# raspberrypi-testcard.net
KiCad netlist of a schematic drawn in EAGLE
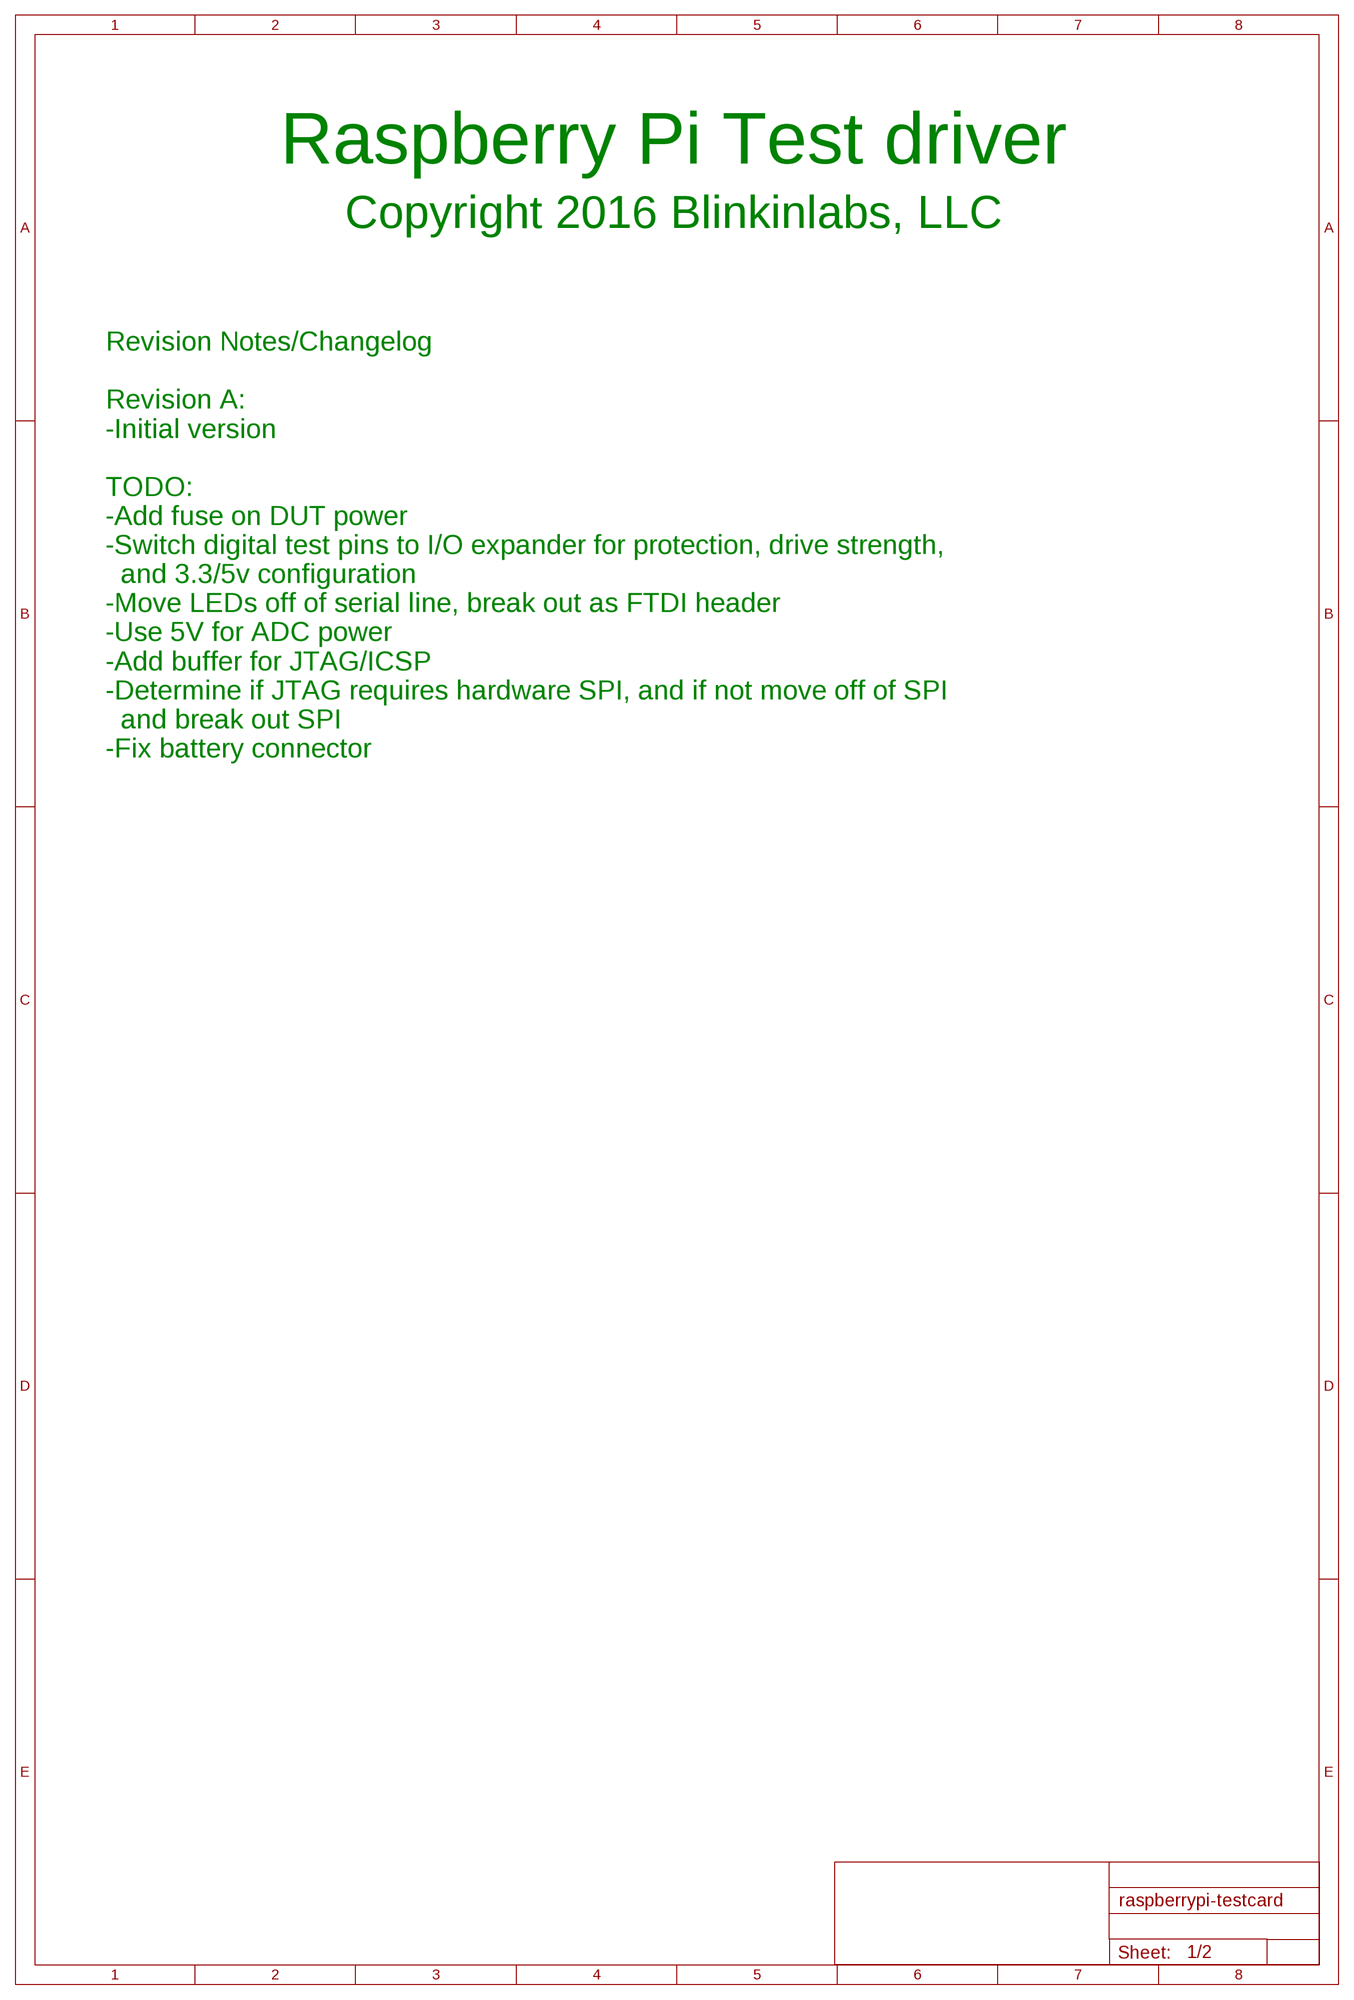
[diagram p0: schematic, sheet 1]
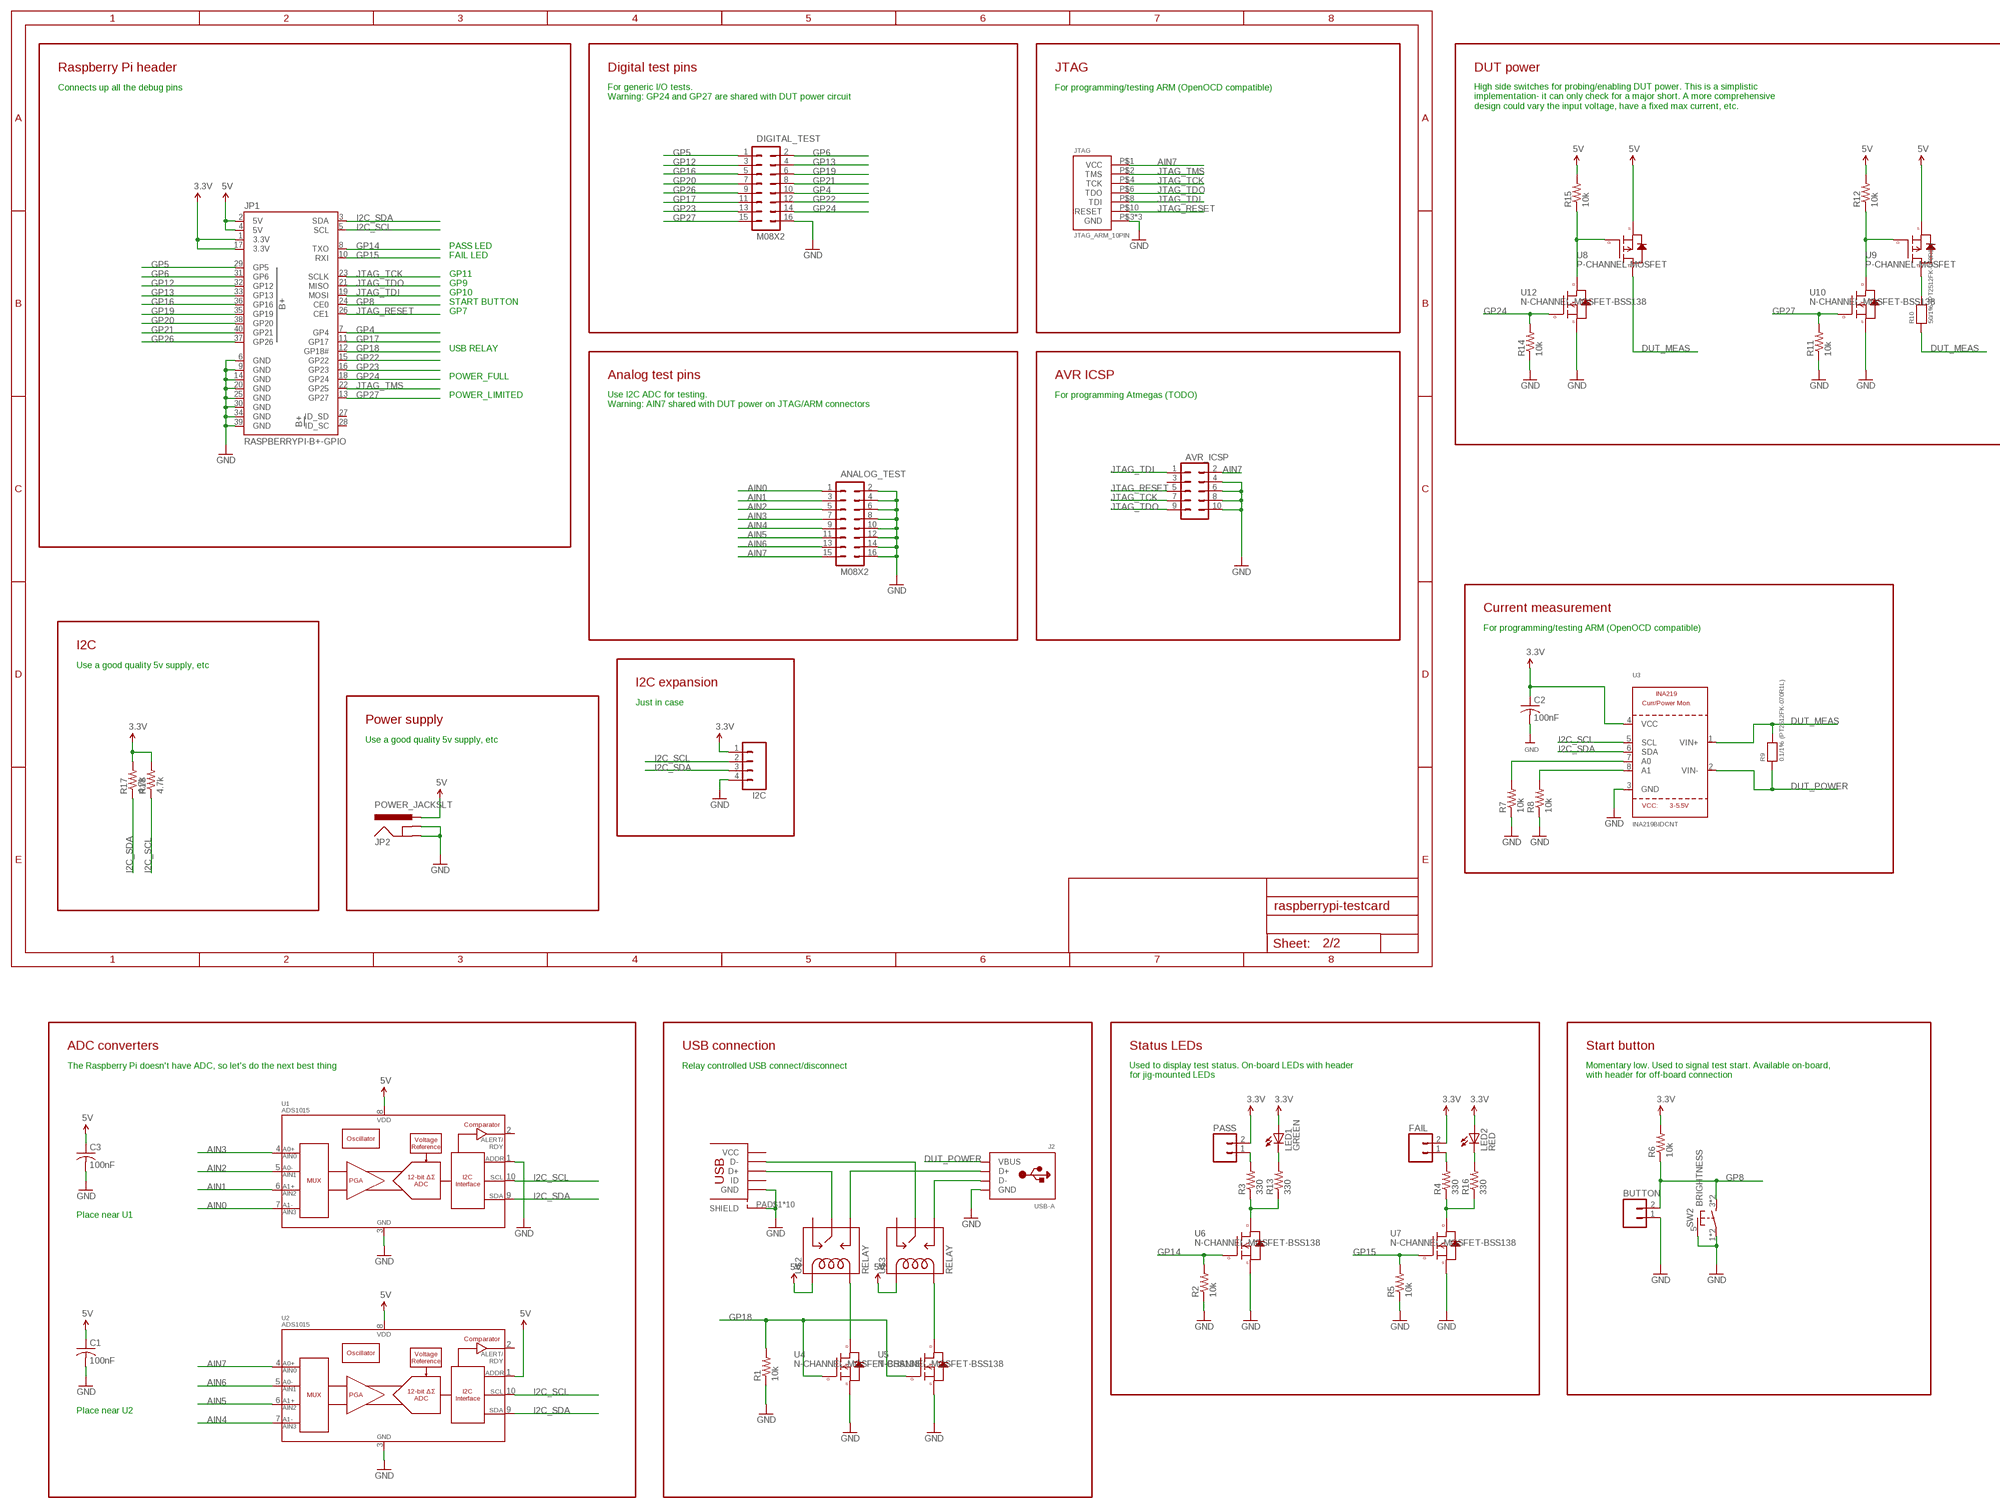
[diagram p1: schematic, sheet 2, part 1 of 2]
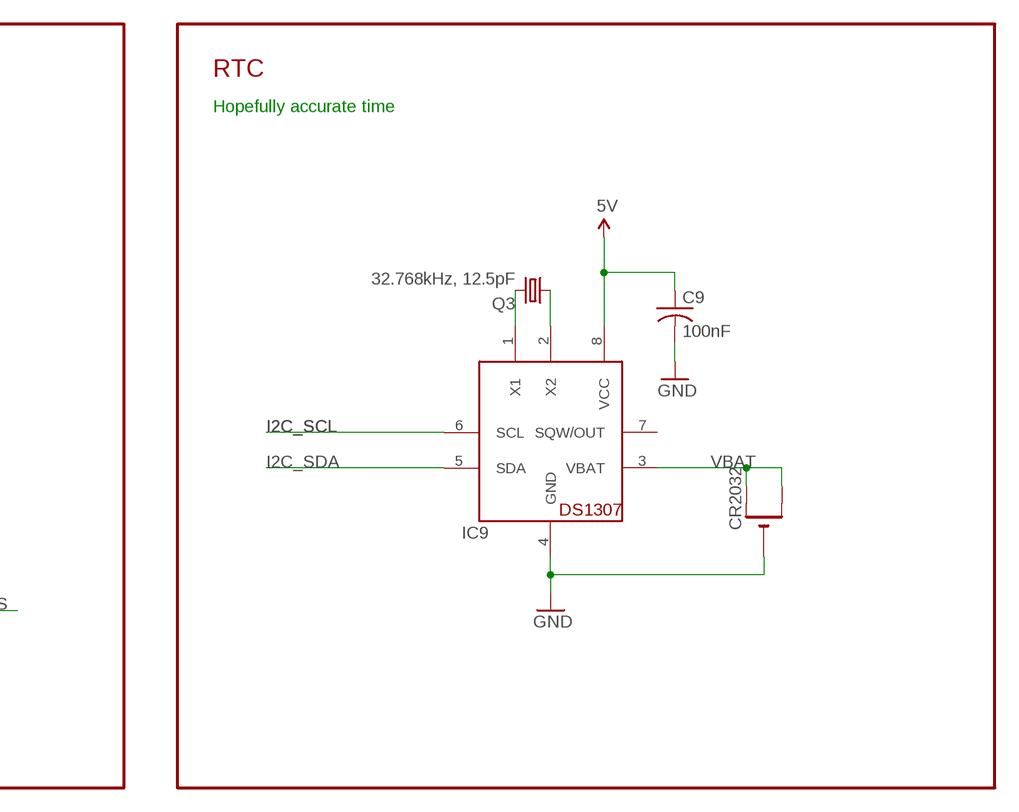
[diagram p2: schematic, sheet 2, part 2 of 2]

(export (version "E")
  (design (tool "Eeschema 10.0.6"))
  (components
    (comp (ref "ANALOG_TEST")
      (value "M08X2")
      (footprint "eagle-import:2X8")
      (libsource (lib "eagle-import") (part "M08X2"))
    )
    (comp (ref "AVR_ICSP")
      (value "M05X2PTH")
      (footprint "eagle-import:AVR_ICSP")
      (libsource (lib "eagle-import") (part "M05X2PTH"))
    )
    (comp (ref "BUTTON")
      (value "M02JST-PTH-2")
      (footprint "eagle-import:JST-2-PTH")
      (libsource (lib "eagle-import") (part "M02JST-PTH-2"))
    )
    (comp (ref "C1")
      (value "100nF")
      (footprint "eagle-import:C0402")
      (libsource (lib "eagle-import") (part "C-USC0402"))
    )
    (comp (ref "C2")
      (value "100nF")
      (footprint "eagle-import:C0402")
      (libsource (lib "eagle-import") (part "C-USC0402"))
    )
    (comp (ref "C3")
      (value "100nF")
      (footprint "eagle-import:C0402")
      (libsource (lib "eagle-import") (part "C-USC0402"))
    )
    (comp (ref "C9")
      (value "100nF")
      (footprint "eagle-import:C0402K")
      (libsource (lib "eagle-import") (part "C-USC0402K"))
    )
    (comp (ref "CR2032")
      (value "CR2032SMT")
      (footprint "eagle-import:CR2032-SMD")
      (libsource (lib "eagle-import") (part "CR2032SMT"))
    )
    (comp (ref "DIGITAL_TEST")
      (value "M08X2")
      (footprint "eagle-import:2X8")
      (libsource (lib "eagle-import") (part "M08X2"))
    )
    (comp (ref "FAIL")
      (value "M02JST-PTH-2")
      (footprint "eagle-import:JST-2-PTH")
      (libsource (lib "eagle-import") (part "M02JST-PTH-2"))
    )
    (comp (ref "I2C")
      (value "M04PTH")
      (footprint "eagle-import:1X04")
      (libsource (lib "eagle-import") (part "M04PTH"))
    )
    (comp (ref "IC9")
      (value "DS1307SO08")
      (footprint "eagle-import:SO08-150")
      (libsource (lib "eagle-import") (part "DS1307SO08"))
    )
    (comp (ref "J1")
      (value "USB_MICROSMT+THRUHULE")
      (footprint "eagle-import:USB_MICRO_THRUHOLE")
      (libsource (lib "eagle-import") (part "USB_MICROSMT+THRUHULE"))
    )
    (comp (ref "J2")
      (value "USB-A")
      (footprint "eagle-import:MOLEX_480371000")
      (libsource (lib "eagle-import") (part "USB-A"))
    )
    (comp (ref "JP1")
      (value "RASPBERRYPI-B+-GPIO")
      (footprint "eagle-import:2X20-SHROUDED")
      (libsource (lib "eagle-import") (part "RASPBERRYPI-B+-GPIO"))
    )
    (comp (ref "JP2")
      (value "POWER_JACKSLT")
      (footprint "eagle-import:POWER_JACK_SLOT")
      (libsource (lib "eagle-import") (part "POWER_JACKSLT"))
    )
    (comp (ref "JTAG")
      (value "JTAG_ARM_10PIN")
      (footprint "eagle-import:2X05-1.27MM-SMD")
      (libsource (lib "eagle-import") (part "JTAG_ARM_10PIN"))
    )
    (comp (ref "LED1")
      (value "GREEN")
      (footprint "eagle-import:CHIP-LED0805")
      (libsource (lib "eagle-import") (part "LEDCHIP-LED0805"))
    )
    (comp (ref "LED2")
      (value "RED")
      (footprint "eagle-import:CHIP-LED0805")
      (libsource (lib "eagle-import") (part "LEDCHIP-LED0805"))
    )
    (comp (ref "PASS")
      (value "M02JST-PTH-2")
      (footprint "eagle-import:JST-2-PTH")
      (libsource (lib "eagle-import") (part "M02JST-PTH-2"))
    )
    (comp (ref "Q3")
      (value "32.768kHz, 12.5pF")
      (footprint "eagle-import:TC26H")
      (libsource (lib "eagle-import") (part "CRYSTALTC26H"))
    )
    (comp (ref "R1")
      (value "10k")
      (footprint "eagle-import:R0402")
      (libsource (lib "eagle-import") (part "R-US_R0402"))
    )
    (comp (ref "R2")
      (value "10k")
      (footprint "eagle-import:R0402")
      (libsource (lib "eagle-import") (part "R-US_R0402"))
    )
    (comp (ref "R3")
      (value "330")
      (footprint "eagle-import:R0402")
      (libsource (lib "eagle-import") (part "R-US_R0402"))
    )
    (comp (ref "R4")
      (value "330")
      (footprint "eagle-import:R0402")
      (libsource (lib "eagle-import") (part "R-US_R0402"))
    )
    (comp (ref "R5")
      (value "10k")
      (footprint "eagle-import:R0402")
      (libsource (lib "eagle-import") (part "R-US_R0402"))
    )
    (comp (ref "R6")
      (value "10k")
      (footprint "eagle-import:R0402")
      (libsource (lib "eagle-import") (part "R-US_R0402"))
    )
    (comp (ref "R7")
      (value "10k")
      (footprint "eagle-import:R0402")
      (libsource (lib "eagle-import") (part "R-US_R0402"))
    )
    (comp (ref "R8")
      (value "10k")
      (footprint "eagle-import:R0402")
      (libsource (lib "eagle-import") (part "R-US_R0402"))
    )
    (comp (ref "R9")
      (value "0.1/1% (PT2512FK-070R1L)")
      (footprint "eagle-import:2512")
      (libsource (lib "eagle-import") (part "RESISTOR2512"))
    )
    (comp (ref "R10")
      (value "50/1% (PT2512FK-070R1L)")
      (footprint "eagle-import:2512")
      (libsource (lib "eagle-import") (part "RESISTOR2512"))
    )
    (comp (ref "R11")
      (value "10k")
      (footprint "eagle-import:R0402")
      (libsource (lib "eagle-import") (part "R-US_R0402"))
    )
    (comp (ref "R12")
      (value "10k")
      (footprint "eagle-import:R0402")
      (libsource (lib "eagle-import") (part "R-US_R0402"))
    )
    (comp (ref "R13")
      (value "330")
      (footprint "eagle-import:R0402")
      (libsource (lib "eagle-import") (part "R-US_R0402"))
    )
    (comp (ref "R14")
      (value "10k")
      (footprint "eagle-import:R0402")
      (libsource (lib "eagle-import") (part "R-US_R0402"))
    )
    (comp (ref "R15")
      (value "10k")
      (footprint "eagle-import:R0402")
      (libsource (lib "eagle-import") (part "R-US_R0402"))
    )
    (comp (ref "R16")
      (value "330")
      (footprint "eagle-import:R0402")
      (libsource (lib "eagle-import") (part "R-US_R0402"))
    )
    (comp (ref "R17")
      (value "4.7k")
      (footprint "eagle-import:R0402")
      (libsource (lib "eagle-import") (part "R-US_R0402"))
    )
    (comp (ref "R18")
      (value "4.7k")
      (footprint "eagle-import:R0402")
      (libsource (lib "eagle-import") (part "R-US_R0402"))
    )
    (comp (ref "SW2")
      (value "BRIGHTNESS")
      (footprint "eagle-import:TD-07XB")
      (libsource (lib "eagle-import") (part "BUTTON_MOMENTARY_GROUND"))
    )
    (comp (ref "U$2")
      (value "RELAY")
      (footprint "eagle-import:RELAY_HK23F-5V")
      (libsource (lib "eagle-import") (part "RELAY"))
    )
    (comp (ref "U$3")
      (value "RELAY")
      (footprint "eagle-import:RELAY_HK23F-5V")
      (libsource (lib "eagle-import") (part "RELAY"))
    )
    (comp (ref "U1")
      (value "ADS1015")
      (footprint "eagle-import:MSOP10")
      (libsource (lib "eagle-import") (part "ADS1015"))
    )
    (comp (ref "U2")
      (value "ADS1015")
      (footprint "eagle-import:MSOP10")
      (libsource (lib "eagle-import") (part "ADS1015"))
    )
    (comp (ref "U3")
      (value "INA219BIDCNT")
      (footprint "eagle-import:SOT23-8")
      (libsource (lib "eagle-import") (part "INA219"))
    )
    (comp (ref "U4")
      (value "N-CHANNEL-MOSFET-BSS138")
      (footprint "eagle-import:SOT23-3")
      (libsource (lib "eagle-import") (part "N-CHANNEL-MOSFET-BSS138"))
    )
    (comp (ref "U5")
      (value "N-CHANNEL-MOSFET-BSS138")
      (footprint "eagle-import:SOT23-3")
      (libsource (lib "eagle-import") (part "N-CHANNEL-MOSFET-BSS138"))
    )
    (comp (ref "U6")
      (value "N-CHANNEL-MOSFET-BSS138")
      (footprint "eagle-import:SOT23-3")
      (libsource (lib "eagle-import") (part "N-CHANNEL-MOSFET-BSS138"))
    )
    (comp (ref "U7")
      (value "N-CHANNEL-MOSFET-BSS138")
      (footprint "eagle-import:SOT23-3")
      (libsource (lib "eagle-import") (part "N-CHANNEL-MOSFET-BSS138"))
    )
    (comp (ref "U8")
      (value "P-CHANNEL-MOSFET")
      (footprint "eagle-import:SOT23-3")
      (libsource (lib "eagle-import") (part "P-CHANNEL-MOSFET"))
    )
    (comp (ref "U9")
      (value "P-CHANNEL-MOSFET")
      (footprint "eagle-import:SOT23-3")
      (libsource (lib "eagle-import") (part "P-CHANNEL-MOSFET"))
    )
    (comp (ref "U10")
      (value "N-CHANNEL-MOSFET-BSS138")
      (footprint "eagle-import:SOT23-3")
      (libsource (lib "eagle-import") (part "N-CHANNEL-MOSFET-BSS138"))
    )
    (comp (ref "U12")
      (value "N-CHANNEL-MOSFET-BSS138")
      (footprint "eagle-import:SOT23-3")
      (libsource (lib "eagle-import") (part "N-CHANNEL-MOSFET-BSS138"))
    )
  )
  (nets
    (net (code "1") (name "3.3V") (class "Default")
      (node (ref "C2") (pin "1") (pinfunction "1_1") (pintype "passive"))
      (node (ref "FAIL") (pin "2") (pinfunction "2_2") (pintype "passive"))
      (node (ref "I2C") (pin "1") (pinfunction "1_1") (pintype "passive"))
      (node (ref "JP1") (pin "1") (pinfunction "3.3V_1") (pintype "power_in"))
      (node (ref "JP1") (pin "17") (pinfunction "3.3V_17") (pintype "power_in"))
      (node (ref "LED1") (pin "A") (pinfunction "A_A") (pintype "passive"))
      (node (ref "LED2") (pin "A") (pinfunction "A_A") (pintype "passive"))
      (node (ref "PASS") (pin "2") (pinfunction "2_2") (pintype "passive"))
      (node (ref "R17") (pin "2") (pinfunction "2_2") (pintype "passive"))
      (node (ref "R18") (pin "2") (pinfunction "2_2") (pintype "passive"))
      (node (ref "R6") (pin "2") (pinfunction "2_2") (pintype "passive"))
      (node (ref "U3") (pin "4") (pinfunction "VCC_4") (pintype "bidirectional"))
    )
    (net (code "2") (name "5V") (class "Default")
      (node (ref "C1") (pin "1") (pinfunction "1_1") (pintype "passive"))
      (node (ref "C3") (pin "1") (pinfunction "1_1") (pintype "passive"))
      (node (ref "C9") (pin "1") (pinfunction "1_1") (pintype "passive"))
      (node (ref "IC9") (pin "8") (pinfunction "VCC_8") (pintype "power_in"))
      (node (ref "JP1") (pin "2") (pinfunction "5V_2") (pintype "power_in"))
      (node (ref "JP1") (pin "4") (pinfunction "5V_4") (pintype "power_in"))
      (node (ref "JP2") (pin "PWR") (pinfunction "PWR_PWR") (pintype "bidirectional"))
      (node (ref "R12") (pin "2") (pinfunction "2_2") (pintype "passive"))
      (node (ref "R15") (pin "2") (pinfunction "2_2") (pintype "passive"))
      (node (ref "U$2") (pin "P$2") (pinfunction "COIL1_P$2") (pintype "bidirectional"))
      (node (ref "U$3") (pin "P$2") (pinfunction "COIL1_P$2") (pintype "bidirectional"))
      (node (ref "U1") (pin "8") (pinfunction "VDD_8") (pintype "bidirectional"))
      (node (ref "U2") (pin "1") (pinfunction "ADDR_1") (pintype "bidirectional"))
      (node (ref "U2") (pin "8") (pinfunction "VDD_8") (pintype "bidirectional"))
      (node (ref "U8") (pin "2") (pinfunction "S_2") (pintype "passive"))
      (node (ref "U9") (pin "2") (pinfunction "S_2") (pintype "passive"))
    )
    (net (code "3") (name "AIN0") (class "Default")
      (node (ref "ANALOG_TEST") (pin "1") (pinfunction "1_1") (pintype "passive"))
      (node (ref "U1") (pin "7") (pinfunction "AIN3_7") (pintype "bidirectional"))
    )
    (net (code "4") (name "AIN1") (class "Default")
      (node (ref "ANALOG_TEST") (pin "3") (pinfunction "3_3") (pintype "passive"))
      (node (ref "U1") (pin "6") (pinfunction "AIN2_6") (pintype "bidirectional"))
    )
    (net (code "5") (name "AIN2") (class "Default")
      (node (ref "ANALOG_TEST") (pin "5") (pinfunction "5_5") (pintype "passive"))
      (node (ref "U1") (pin "5") (pinfunction "AIN1_5") (pintype "bidirectional"))
    )
    (net (code "6") (name "AIN3") (class "Default")
      (node (ref "ANALOG_TEST") (pin "7") (pinfunction "7_7") (pintype "passive"))
      (node (ref "U1") (pin "4") (pinfunction "AIN0_4") (pintype "bidirectional"))
    )
    (net (code "7") (name "AIN4") (class "Default")
      (node (ref "ANALOG_TEST") (pin "9") (pinfunction "9_9") (pintype "passive"))
      (node (ref "U2") (pin "7") (pinfunction "AIN3_7") (pintype "bidirectional"))
    )
    (net (code "8") (name "AIN5") (class "Default")
      (node (ref "ANALOG_TEST") (pin "11") (pinfunction "11_11") (pintype "passive"))
      (node (ref "U2") (pin "6") (pinfunction "AIN2_6") (pintype "bidirectional"))
    )
    (net (code "9") (name "AIN6") (class "Default")
      (node (ref "ANALOG_TEST") (pin "13") (pinfunction "13_13") (pintype "passive"))
      (node (ref "U2") (pin "5") (pinfunction "AIN1_5") (pintype "bidirectional"))
    )
    (net (code "10") (name "AIN7") (class "Default")
      (node (ref "ANALOG_TEST") (pin "15") (pinfunction "15_15") (pintype "passive"))
      (node (ref "AVR_ICSP") (pin "2") (pinfunction "2_2") (pintype "passive"))
      (node (ref "JTAG") (pin "P$1") (pinfunction "VCC_P$1") (pintype "power_in"))
      (node (ref "U2") (pin "4") (pinfunction "AIN0_4") (pintype "bidirectional"))
    )
    (net (code "11") (name "DUT_MEAS") (class "Default")
      (node (ref "R10") (pin "1") (pinfunction "1_1") (pintype "passive"))
      (node (ref "R9") (pin "2") (pinfunction "2_2") (pintype "passive"))
      (node (ref "U3") (pin "1") (pinfunction "VIN+_1") (pintype "bidirectional"))
      (node (ref "U8") (pin "3") (pinfunction "D_3") (pintype "passive"))
    )
    (net (code "12") (name "DUT_POWER") (class "Default")
      (node (ref "J2") (pin "1") (pinfunction "VBUS_1") (pintype "power_in"))
      (node (ref "R9") (pin "1") (pinfunction "1_1") (pintype "passive"))
      (node (ref "U3") (pin "2") (pinfunction "VIN-_2") (pintype "bidirectional"))
    )
    (net (code "13") (name "GND") (class "Default")
      (node (ref "ANALOG_TEST") (pin "10") (pinfunction "10_10") (pintype "passive"))
      (node (ref "ANALOG_TEST") (pin "12") (pinfunction "12_12") (pintype "passive"))
      (node (ref "ANALOG_TEST") (pin "14") (pinfunction "14_14") (pintype "passive"))
      (node (ref "ANALOG_TEST") (pin "16") (pinfunction "16_16") (pintype "passive"))
      (node (ref "ANALOG_TEST") (pin "2") (pinfunction "2_2") (pintype "passive"))
      (node (ref "ANALOG_TEST") (pin "4") (pinfunction "4_4") (pintype "passive"))
      (node (ref "ANALOG_TEST") (pin "6") (pinfunction "6_6") (pintype "passive"))
      (node (ref "ANALOG_TEST") (pin "8") (pinfunction "8_8") (pintype "passive"))
      (node (ref "AVR_ICSP") (pin "10") (pinfunction "10_10") (pintype "passive"))
      (node (ref "AVR_ICSP") (pin "4") (pinfunction "4_4") (pintype "passive"))
      (node (ref "AVR_ICSP") (pin "6") (pinfunction "6_6") (pintype "passive"))
      (node (ref "AVR_ICSP") (pin "8") (pinfunction "8_8") (pintype "passive"))
      (node (ref "BUTTON") (pin "1") (pinfunction "1_1") (pintype "passive"))
      (node (ref "C1") (pin "2") (pinfunction "2_2") (pintype "passive"))
      (node (ref "C2") (pin "2") (pinfunction "2_2") (pintype "passive"))
      (node (ref "C3") (pin "2") (pinfunction "2_2") (pintype "passive"))
      (node (ref "C9") (pin "2") (pinfunction "2_2") (pintype "passive"))
      (node (ref "CR2032") (pin "-") (pinfunction "-_-") (pintype "passive"))
      (node (ref "DIGITAL_TEST") (pin "16") (pinfunction "16_16") (pintype "passive"))
      (node (ref "I2C") (pin "4") (pinfunction "4_4") (pintype "passive"))
      (node (ref "IC9") (pin "4") (pinfunction "GND_4") (pintype "power_in"))
      (node (ref "J1") (pin "PAD$1") (pinfunction "SHIELD_PAD$1") (pintype "bidirectional"))
      (node (ref "J1") (pin "PAD$10") (pinfunction "SHIELD_PAD$10") (pintype "bidirectional"))
      (node (ref "J1") (pin "PAD$2") (pinfunction "SHIELD_PAD$2") (pintype "bidirectional"))
      (node (ref "J1") (pin "PAD$3") (pinfunction "SHIELD_PAD$3") (pintype "bidirectional"))
      (node (ref "J1") (pin "PAD$4") (pinfunction "SHIELD_PAD$4") (pintype "bidirectional"))
      (node (ref "J1") (pin "PAD$5") (pinfunction "SHIELD_PAD$5") (pintype "bidirectional"))
      (node (ref "J1") (pin "PAD$6") (pinfunction "SHIELD_PAD$6") (pintype "bidirectional"))
      (node (ref "J1") (pin "PAD$7") (pinfunction "SHIELD_PAD$7") (pintype "bidirectional"))
      (node (ref "J1") (pin "PAD$8") (pinfunction "SHIELD_PAD$8") (pintype "bidirectional"))
      (node (ref "J1") (pin "PAD$9") (pinfunction "SHIELD_PAD$9") (pintype "bidirectional"))
      (node (ref "J1") (pin "PIN$5") (pinfunction "GND_PIN$5") (pintype "bidirectional"))
      (node (ref "J2") (pin "4") (pinfunction "GND_4") (pintype "power_in"))
      (node (ref "JP1") (pin "14") (pinfunction "GND_14") (pintype "power_in"))
      (node (ref "JP1") (pin "20") (pinfunction "GND_20") (pintype "power_in"))
      (node (ref "JP1") (pin "25") (pinfunction "GND_25") (pintype "power_in"))
      (node (ref "JP1") (pin "30") (pinfunction "GND_30") (pintype "power_in"))
      (node (ref "JP1") (pin "34") (pinfunction "GND_34") (pintype "power_in"))
      (node (ref "JP1") (pin "39") (pinfunction "GND_39") (pintype "power_in"))
      (node (ref "JP1") (pin "6") (pinfunction "GND_6") (pintype "power_in"))
      (node (ref "JP1") (pin "9") (pinfunction "GND_9") (pintype "power_in"))
      (node (ref "JP2") (pin "GND@1") (pinfunction "GNDBREAK_GND@1") (pintype "bidirectional"))
      (node (ref "JP2") (pin "GND@2") (pinfunction "GND_GND@2") (pintype "bidirectional"))
      (node (ref "JTAG") (pin "P$3") (pinfunction "GND_P$3") (pintype "power_in"))
      (node (ref "JTAG") (pin "P$5") (pinfunction "GND_P$5") (pintype "power_in"))
      (node (ref "JTAG") (pin "P$9") (pinfunction "GND_P$9") (pintype "power_in"))
      (node (ref "R1") (pin "1") (pinfunction "1_1") (pintype "passive"))
      (node (ref "R11") (pin "1") (pinfunction "1_1") (pintype "passive"))
      (node (ref "R14") (pin "1") (pinfunction "1_1") (pintype "passive"))
      (node (ref "R2") (pin "1") (pinfunction "1_1") (pintype "passive"))
      (node (ref "R5") (pin "1") (pinfunction "1_1") (pintype "passive"))
      (node (ref "R7") (pin "1") (pinfunction "1_1") (pintype "passive"))
      (node (ref "R8") (pin "1") (pinfunction "1_1") (pintype "passive"))
      (node (ref "SW2") (pin "1") (pinfunction "P_1") (pintype "passive"))
      (node (ref "SW2") (pin "2") (pinfunction "P_2") (pintype "passive"))
      (node (ref "SW2") (pin "5") (pinfunction "SHIELD_5") (pintype "passive"))
      (node (ref "U1") (pin "1") (pinfunction "ADDR_1") (pintype "bidirectional"))
      (node (ref "U1") (pin "3") (pinfunction "VSS_3") (pintype "bidirectional"))
      (node (ref "U10") (pin "2") (pinfunction "S_2") (pintype "passive"))
      (node (ref "U12") (pin "2") (pinfunction "S_2") (pintype "passive"))
      (node (ref "U2") (pin "3") (pinfunction "VSS_3") (pintype "bidirectional"))
      (node (ref "U3") (pin "3") (pinfunction "GND_3") (pintype "bidirectional"))
      (node (ref "U4") (pin "2") (pinfunction "S_2") (pintype "passive"))
      (node (ref "U5") (pin "2") (pinfunction "S_2") (pintype "passive"))
      (node (ref "U6") (pin "2") (pinfunction "S_2") (pintype "passive"))
      (node (ref "U7") (pin "2") (pinfunction "S_2") (pintype "passive"))
    )
    (net (code "14") (name "GP4") (class "Default")
      (node (ref "DIGITAL_TEST") (pin "10") (pinfunction "10_10") (pintype "passive"))
      (node (ref "JP1") (pin "7") (pinfunction "GP4_7") (pintype "bidirectional"))
    )
    (net (code "15") (name "GP5") (class "Default")
      (node (ref "DIGITAL_TEST") (pin "1") (pinfunction "1_1") (pintype "passive"))
      (node (ref "JP1") (pin "29") (pinfunction "GP5_29") (pintype "bidirectional"))
    )
    (net (code "16") (name "GP6") (class "Default")
      (node (ref "DIGITAL_TEST") (pin "2") (pinfunction "2_2") (pintype "passive"))
      (node (ref "JP1") (pin "31") (pinfunction "GP6_31") (pintype "bidirectional"))
    )
    (net (code "17") (name "GP8") (class "Default")
      (node (ref "BUTTON") (pin "2") (pinfunction "2_2") (pintype "passive"))
      (node (ref "JP1") (pin "24") (pinfunction "CE0_24") (pintype "output"))
      (node (ref "R6") (pin "1") (pinfunction "1_1") (pintype "passive"))
      (node (ref "SW2") (pin "3") (pinfunction "S_3") (pintype "passive"))
      (node (ref "SW2") (pin "4") (pinfunction "S_4") (pintype "passive"))
    )
    (net (code "18") (name "GP12") (class "Default")
      (node (ref "DIGITAL_TEST") (pin "3") (pinfunction "3_3") (pintype "passive"))
      (node (ref "JP1") (pin "32") (pinfunction "GP12_32") (pintype "bidirectional"))
    )
    (net (code "19") (name "GP13") (class "Default")
      (node (ref "DIGITAL_TEST") (pin "4") (pinfunction "4_4") (pintype "passive"))
      (node (ref "JP1") (pin "33") (pinfunction "GP13_33") (pintype "bidirectional"))
    )
    (net (code "20") (name "GP14") (class "Default")
      (node (ref "JP1") (pin "8") (pinfunction "TXO_8") (pintype "output"))
      (node (ref "R2") (pin "2") (pinfunction "2_2") (pintype "passive"))
      (node (ref "U6") (pin "1") (pinfunction "G_1") (pintype "passive"))
    )
    (net (code "21") (name "GP15") (class "Default")
      (node (ref "JP1") (pin "10") (pinfunction "RXI_10") (pintype "input"))
      (node (ref "R5") (pin "2") (pinfunction "2_2") (pintype "passive"))
      (node (ref "U7") (pin "1") (pinfunction "G_1") (pintype "passive"))
    )
    (net (code "22") (name "GP16") (class "Default")
      (node (ref "DIGITAL_TEST") (pin "5") (pinfunction "5_5") (pintype "passive"))
      (node (ref "JP1") (pin "36") (pinfunction "GP16_36") (pintype "bidirectional"))
    )
    (net (code "23") (name "GP17") (class "Default")
      (node (ref "DIGITAL_TEST") (pin "11") (pinfunction "11_11") (pintype "passive"))
      (node (ref "JP1") (pin "11") (pinfunction "GP17_11") (pintype "bidirectional"))
    )
    (net (code "24") (name "GP18") (class "Default")
      (node (ref "JP1") (pin "12") (pinfunction "GP18#_12") (pintype "bidirectional"))
      (node (ref "R1") (pin "2") (pinfunction "2_2") (pintype "passive"))
      (node (ref "U4") (pin "1") (pinfunction "G_1") (pintype "passive"))
      (node (ref "U5") (pin "1") (pinfunction "G_1") (pintype "passive"))
    )
    (net (code "25") (name "GP19") (class "Default")
      (node (ref "DIGITAL_TEST") (pin "6") (pinfunction "6_6") (pintype "passive"))
      (node (ref "JP1") (pin "35") (pinfunction "GP19_35") (pintype "bidirectional"))
    )
    (net (code "26") (name "GP20") (class "Default")
      (node (ref "DIGITAL_TEST") (pin "7") (pinfunction "7_7") (pintype "passive"))
      (node (ref "JP1") (pin "38") (pinfunction "GP20_38") (pintype "bidirectional"))
    )
    (net (code "27") (name "GP21") (class "Default")
      (node (ref "DIGITAL_TEST") (pin "8") (pinfunction "8_8") (pintype "passive"))
      (node (ref "JP1") (pin "40") (pinfunction "GP21_40") (pintype "bidirectional"))
    )
    (net (code "28") (name "GP22") (class "Default")
      (node (ref "DIGITAL_TEST") (pin "12") (pinfunction "12_12") (pintype "passive"))
      (node (ref "JP1") (pin "15") (pinfunction "GP22_15") (pintype "bidirectional"))
    )
    (net (code "29") (name "GP23") (class "Default")
      (node (ref "DIGITAL_TEST") (pin "13") (pinfunction "13_13") (pintype "passive"))
      (node (ref "JP1") (pin "16") (pinfunction "GP23_16") (pintype "bidirectional"))
    )
    (net (code "30") (name "GP24") (class "Default")
      (node (ref "DIGITAL_TEST") (pin "14") (pinfunction "14_14") (pintype "passive"))
      (node (ref "JP1") (pin "18") (pinfunction "GP24_18") (pintype "bidirectional"))
      (node (ref "R14") (pin "2") (pinfunction "2_2") (pintype "passive"))
      (node (ref "U12") (pin "1") (pinfunction "G_1") (pintype "passive"))
    )
    (net (code "31") (name "GP26") (class "Default")
      (node (ref "DIGITAL_TEST") (pin "9") (pinfunction "9_9") (pintype "passive"))
      (node (ref "JP1") (pin "37") (pinfunction "GP26_37") (pintype "bidirectional"))
    )
    (net (code "32") (name "GP27") (class "Default")
      (node (ref "DIGITAL_TEST") (pin "15") (pinfunction "15_15") (pintype "passive"))
      (node (ref "JP1") (pin "13") (pinfunction "GP27_13") (pintype "bidirectional"))
      (node (ref "R11") (pin "2") (pinfunction "2_2") (pintype "passive"))
      (node (ref "U10") (pin "1") (pinfunction "G_1") (pintype "passive"))
    )
    (net (code "33") (name "I2C_SCL") (class "Default")
      (node (ref "I2C") (pin "2") (pinfunction "2_2") (pintype "passive"))
      (node (ref "IC9") (pin "6") (pinfunction "SCL_6") (pintype "bidirectional"))
      (node (ref "JP1") (pin "5") (pinfunction "SCL_5") (pintype "bidirectional"))
      (node (ref "R18") (pin "1") (pinfunction "1_1") (pintype "passive"))
      (node (ref "U1") (pin "10") (pinfunction "SCL_10") (pintype "bidirectional"))
      (node (ref "U2") (pin "10") (pinfunction "SCL_10") (pintype "bidirectional"))
      (node (ref "U3") (pin "5") (pinfunction "SCL_5") (pintype "bidirectional"))
    )
    (net (code "34") (name "I2C_SDA") (class "Default")
      (node (ref "I2C") (pin "3") (pinfunction "3_3") (pintype "passive"))
      (node (ref "IC9") (pin "5") (pinfunction "SDA_5") (pintype "bidirectional"))
      (node (ref "JP1") (pin "3") (pinfunction "SDA_3") (pintype "bidirectional"))
      (node (ref "R17") (pin "1") (pinfunction "1_1") (pintype "passive"))
      (node (ref "U1") (pin "9") (pinfunction "SDA_9") (pintype "bidirectional"))
      (node (ref "U2") (pin "9") (pinfunction "SDA_9") (pintype "bidirectional"))
      (node (ref "U3") (pin "6") (pinfunction "SDA_6") (pintype "bidirectional"))
    )
    (net (code "35") (name "JTAG_RESET") (class "Default")
      (node (ref "AVR_ICSP") (pin "5") (pinfunction "5_5") (pintype "passive"))
      (node (ref "JP1") (pin "26") (pinfunction "CE1_26") (pintype "output"))
      (node (ref "JTAG") (pin "P$10") (pinfunction "RESET_P$10") (pintype "bidirectional"))
    )
    (net (code "36") (name "JTAG_TCK") (class "Default")
      (node (ref "AVR_ICSP") (pin "7") (pinfunction "7_7") (pintype "passive"))
      (node (ref "JP1") (pin "23") (pinfunction "SCLK_23") (pintype "output"))
      (node (ref "JTAG") (pin "P$4") (pinfunction "TCK_P$4") (pintype "bidirectional"))
    )
    (net (code "37") (name "JTAG_TDI") (class "Default")
      (node (ref "AVR_ICSP") (pin "1") (pinfunction "1_1") (pintype "passive"))
      (node (ref "JP1") (pin "19") (pinfunction "MOSI_19") (pintype "output"))
      (node (ref "JTAG") (pin "P$8") (pinfunction "TDI_P$8") (pintype "bidirectional"))
    )
    (net (code "38") (name "JTAG_TDO") (class "Default")
      (node (ref "AVR_ICSP") (pin "9") (pinfunction "9_9") (pintype "passive"))
      (node (ref "JP1") (pin "21") (pinfunction "MISO_21") (pintype "input"))
      (node (ref "JTAG") (pin "P$6") (pinfunction "TDO_P$6") (pintype "bidirectional"))
    )
    (net (code "39") (name "JTAG_TMS") (class "Default")
      (node (ref "JP1") (pin "22") (pinfunction "GP25_22") (pintype "bidirectional"))
      (node (ref "JTAG") (pin "P$2") (pinfunction "TMS_P$2") (pintype "bidirectional"))
    )
    (net (code "40") (name "Net-(FAIL-Pad1)") (class "Default")
      (node (ref "FAIL") (pin "1") (pinfunction "1_1") (pintype "passive"))
      (node (ref "R4") (pin "2") (pinfunction "2_2") (pintype "passive"))
    )
    (net (code "41") (name "Net-(IC9-X1)") (class "Default")
      (node (ref "IC9") (pin "1") (pinfunction "X1_1") (pintype "passive"))
      (node (ref "Q3") (pin "2") (pinfunction "2_2") (pintype "passive"))
    )
    (net (code "42") (name "Net-(IC9-X2)") (class "Default")
      (node (ref "IC9") (pin "2") (pinfunction "X2_2") (pintype "passive"))
      (node (ref "Q3") (pin "1") (pinfunction "1_1") (pintype "passive"))
    )
    (net (code "43") (name "Net-(J1-D+)") (class "Default")
      (node (ref "J1") (pin "PIN$3") (pinfunction "D+_PIN$3") (pintype "bidirectional"))
      (node (ref "U$2") (pin "P$1") (pinfunction "MAIN_P$1") (pintype "bidirectional"))
      (node (ref "U$2") (pin "P$6") (pinfunction "MAIN_P$6") (pintype "bidirectional"))
    )
    (net (code "44") (name "Net-(J1-D-)") (class "Default")
      (node (ref "J1") (pin "PIN$2") (pinfunction "D-_PIN$2") (pintype "bidirectional"))
      (node (ref "U$3") (pin "P$1") (pinfunction "MAIN_P$1") (pintype "bidirectional"))
      (node (ref "U$3") (pin "P$6") (pinfunction "MAIN_P$6") (pintype "bidirectional"))
    )
    (net (code "45") (name "Net-(J2-D+)") (class "Default")
      (node (ref "J2") (pin "3") (pinfunction "D+_3") (pintype "bidirectional"))
      (node (ref "U$2") (pin "P$3") (pinfunction "NO_P$3") (pintype "bidirectional"))
    )
    (net (code "46") (name "Net-(J2-D-)") (class "Default")
      (node (ref "J2") (pin "2") (pinfunction "D-_2") (pintype "bidirectional"))
      (node (ref "U$3") (pin "P$3") (pinfunction "NO_P$3") (pintype "bidirectional"))
    )
    (net (code "47") (name "Net-(LED1-PadC)") (class "Default")
      (node (ref "LED1") (pin "C") (pinfunction "C_C") (pintype "passive"))
      (node (ref "R13") (pin "2") (pinfunction "2_2") (pintype "passive"))
    )
    (net (code "48") (name "Net-(LED2-PadC)") (class "Default")
      (node (ref "LED2") (pin "C") (pinfunction "C_C") (pintype "passive"))
      (node (ref "R16") (pin "2") (pinfunction "2_2") (pintype "passive"))
    )
    (net (code "49") (name "Net-(PASS-Pad1)") (class "Default")
      (node (ref "PASS") (pin "1") (pinfunction "1_1") (pintype "passive"))
      (node (ref "R3") (pin "2") (pinfunction "2_2") (pintype "passive"))
    )
    (net (code "50") (name "Net-(U$2-COIL2)") (class "Default")
      (node (ref "U$2") (pin "P$5") (pinfunction "COIL2_P$5") (pintype "bidirectional"))
      (node (ref "U4") (pin "3") (pinfunction "D_3") (pintype "passive"))
    )
    (net (code "51") (name "Net-(U$3-COIL2)") (class "Default")
      (node (ref "U$3") (pin "P$5") (pinfunction "COIL2_P$5") (pintype "bidirectional"))
      (node (ref "U5") (pin "3") (pinfunction "D_3") (pintype "passive"))
    )
    (net (code "52") (name "Net-(U3-A0)") (class "Default")
      (node (ref "R7") (pin "2") (pinfunction "2_2") (pintype "passive"))
      (node (ref "U3") (pin "7") (pinfunction "A0_7") (pintype "bidirectional"))
    )
    (net (code "53") (name "Net-(U3-A1)") (class "Default")
      (node (ref "R8") (pin "2") (pinfunction "2_2") (pintype "passive"))
      (node (ref "U3") (pin "8") (pinfunction "A1_8") (pintype "bidirectional"))
    )
    (net (code "54") (name "Net-(U6-D)") (class "Default")
      (node (ref "R13") (pin "1") (pinfunction "1_1") (pintype "passive"))
      (node (ref "R3") (pin "1") (pinfunction "1_1") (pintype "passive"))
      (node (ref "U6") (pin "3") (pinfunction "D_3") (pintype "passive"))
    )
    (net (code "55") (name "Net-(U7-D)") (class "Default")
      (node (ref "R16") (pin "1") (pinfunction "1_1") (pintype "passive"))
      (node (ref "R4") (pin "1") (pinfunction "1_1") (pintype "passive"))
      (node (ref "U7") (pin "3") (pinfunction "D_3") (pintype "passive"))
    )
    (net (code "56") (name "Net-(U9-D)") (class "Default")
      (node (ref "R10") (pin "2") (pinfunction "2_2") (pintype "passive"))
      (node (ref "U9") (pin "3") (pinfunction "D_3") (pintype "passive"))
    )
    (net (code "57") (name "Net-(U10-D)") (class "Default")
      (node (ref "R12") (pin "1") (pinfunction "1_1") (pintype "passive"))
      (node (ref "U10") (pin "3") (pinfunction "D_3") (pintype "passive"))
      (node (ref "U9") (pin "1") (pinfunction "G_1") (pintype "passive"))
    )
    (net (code "58") (name "Net-(U12-D)") (class "Default")
      (node (ref "R15") (pin "1") (pinfunction "1_1") (pintype "passive"))
      (node (ref "U12") (pin "3") (pinfunction "D_3") (pintype "passive"))
      (node (ref "U8") (pin "1") (pinfunction "G_1") (pintype "passive"))
    )
    (net (code "59") (name "VBAT") (class "Default")
      (node (ref "CR2032") (pin "+$1") (pinfunction "+_+$1") (pintype "passive"))
      (node (ref "CR2032") (pin "+$2") (pinfunction "+1_+$2") (pintype "passive"))
      (node (ref "IC9") (pin "3") (pinfunction "VBAT_3") (pintype "power_in"))
    )
    (net (code "60") (name "unconnected-(AVR_ICSP-Pad3)") (class "Default")
      (node (ref "AVR_ICSP") (pin "3") (pinfunction "3_3") (pintype "passive"))
    )
    (net (code "61") (name "unconnected-(IC9-SQW{slash}OUT-Pad7)") (class "Default")
      (node (ref "IC9") (pin "7") (pinfunction "SQW/OUT_7") (pintype "bidirectional"))
    )
    (net (code "62") (name "unconnected-(J1-ID-PadPIN$4)") (class "Default")
      (node (ref "J1") (pin "PIN$4") (pinfunction "ID_PIN$4") (pintype "bidirectional"))
    )
    (net (code "63") (name "unconnected-(J1-VCC-PadPIN$1)") (class "Default")
      (node (ref "J1") (pin "PIN$1") (pinfunction "VCC_PIN$1") (pintype "bidirectional"))
    )
    (net (code "64") (name "unconnected-(JP1-ID_SC-Pad28)") (class "Default")
      (node (ref "JP1") (pin "28") (pinfunction "ID_SC_28") (pintype "bidirectional"))
    )
    (net (code "65") (name "unconnected-(JP1-ID_SD-Pad27)") (class "Default")
      (node (ref "JP1") (pin "27") (pinfunction "ID_SD_27") (pintype "bidirectional"))
    )
    (net (code "66") (name "unconnected-(U$2-NC-PadP$4)") (class "Default")
      (node (ref "U$2") (pin "P$4") (pinfunction "NC_P$4") (pintype "bidirectional"))
    )
    (net (code "67") (name "unconnected-(U$3-NC-PadP$4)") (class "Default")
      (node (ref "U$3") (pin "P$4") (pinfunction "NC_P$4") (pintype "bidirectional"))
    )
    (net (code "68") (name "unconnected-(U1-ALERT{slash}RDY-Pad2)") (class "Default")
      (node (ref "U1") (pin "2") (pinfunction "ALERT/RDY_2") (pintype "bidirectional"))
    )
    (net (code "69") (name "unconnected-(U2-ALERT{slash}RDY-Pad2)") (class "Default")
      (node (ref "U2") (pin "2") (pinfunction "ALERT/RDY_2") (pintype "bidirectional"))
    )
  )
)
